# OSPLC2_2_CPU1.net
KiCad netlist of a schematic drawn in Altium Designer
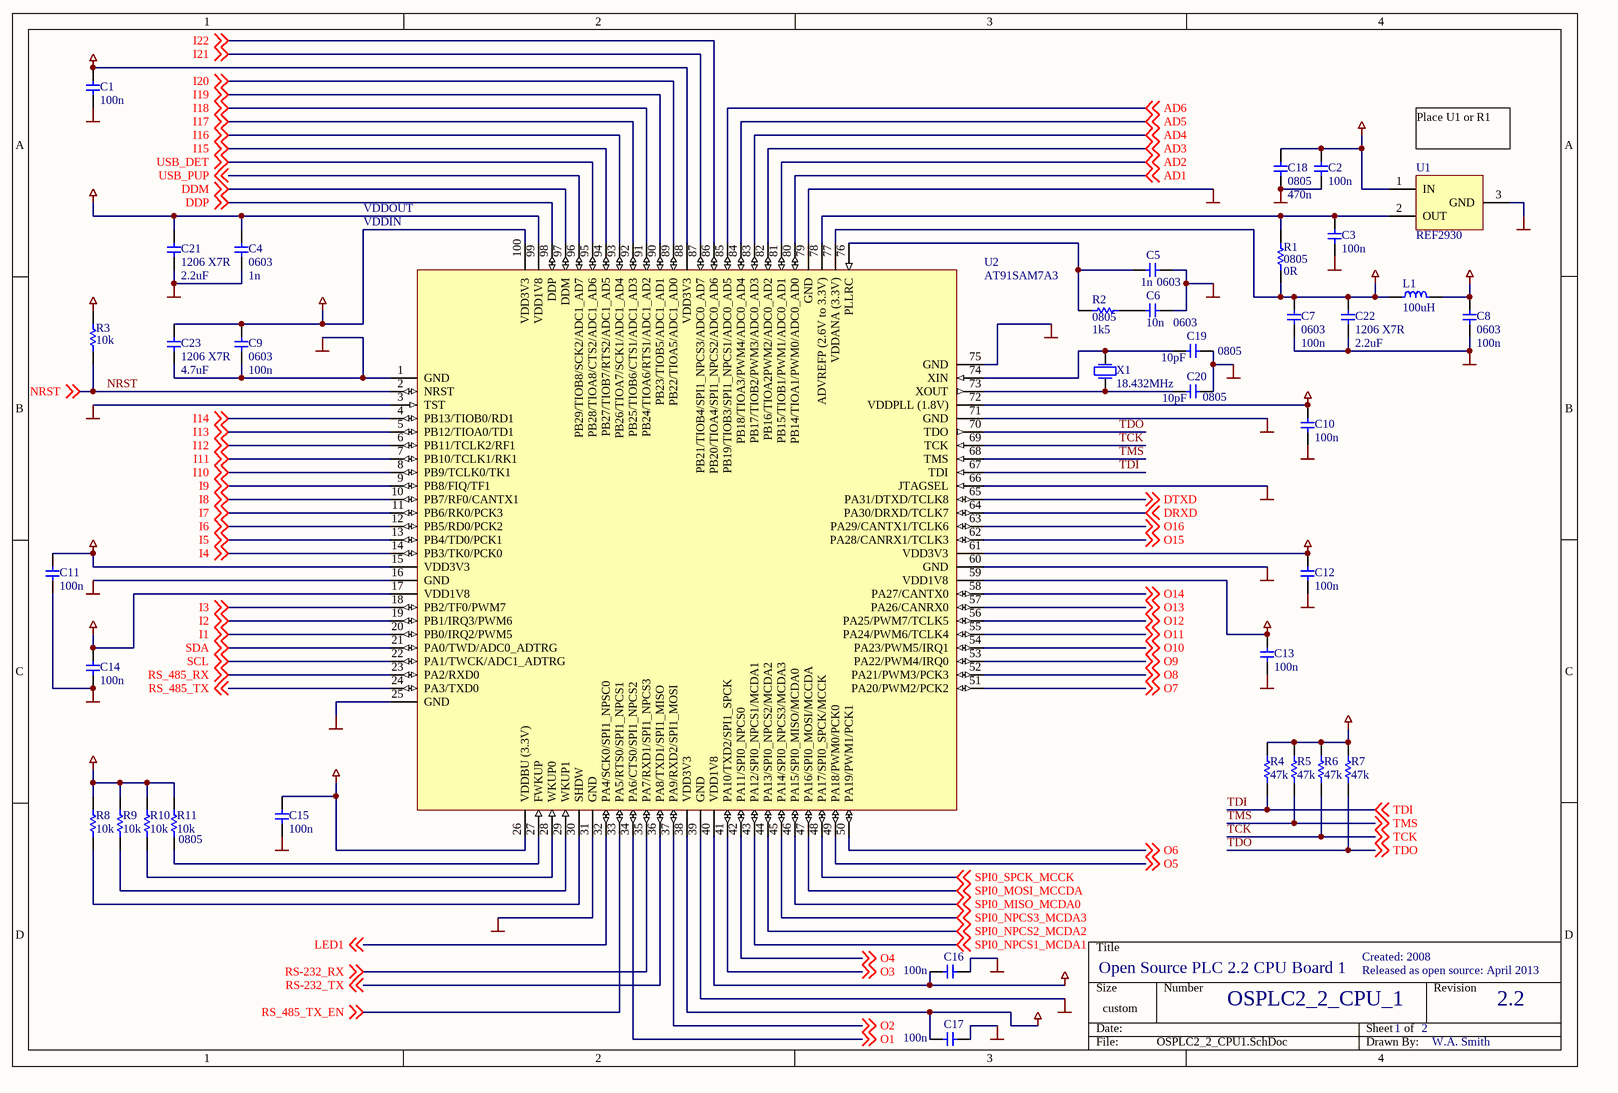
[diagram p0: OSPLC2_2_CPU1.SchDoc]

(export (version "E")
  (design (tool "Eeschema 10.0.6"))
  (components
    (comp (ref "C1")
      (value "0603")
      (footprint "0603")
      (description "0603 footprint non-polorised capacitor")
      (fields (field (name "ALTIUM_VALUE") "100n"))
      (libsource (lib "Integrated Comp_lib") (part "CAP_0603"))
    )
    (comp (ref "C2")
      (value "0603")
      (footprint "0603")
      (description "0603 footprint non-polorised capacitor")
      (fields (field (name "ALTIUM_VALUE") "100n"))
      (libsource (lib "Integrated Comp_lib") (part "CAP_0603"))
    )
    (comp (ref "C3")
      (value "0603")
      (footprint "0603")
      (description "0603 footprint non-polorised capacitor")
      (fields (field (name "ALTIUM_VALUE") "100n"))
      (libsource (lib "Integrated Comp_lib") (part "CAP_0603"))
    )
    (comp (ref "C4")
      (value "0603")
      (footprint "0603")
      (description "0603 footprint non-polorised capacitor")
      (fields (field (name "ALTIUM_VALUE") "1n"))
      (libsource (lib "Integrated Comp_lib") (part "CAP_0603"))
    )
    (comp (ref "C5")
      (value "0603")
      (footprint "0603")
      (description "0603 footprint non-polorised capacitor")
      (fields (field (name "ALTIUM_VALUE") "1n"))
      (libsource (lib "Integrated Comp_lib") (part "CAP_0603"))
    )
    (comp (ref "C6")
      (value "0603")
      (footprint "0603")
      (description "0603 footprint non-polorised capacitor")
      (fields (field (name "ALTIUM_VALUE") "10n"))
      (libsource (lib "Integrated Comp_lib") (part "CAP_0603"))
    )
    (comp (ref "C7")
      (value "0603")
      (footprint "0603")
      (description "0603 footprint non-polorised capacitor")
      (fields (field (name "ALTIUM_VALUE") "100n"))
      (libsource (lib "Integrated Comp_lib") (part "CAP_0603"))
    )
    (comp (ref "C8")
      (value "0603")
      (footprint "0603")
      (description "0603 footprint non-polorised capacitor")
      (fields (field (name "ALTIUM_VALUE") "100n"))
      (libsource (lib "Integrated Comp_lib") (part "CAP_0603"))
    )
    (comp (ref "C9")
      (value "0603")
      (footprint "0603")
      (description "0603 footprint non-polorised capacitor")
      (fields (field (name "ALTIUM_VALUE") "100n"))
      (libsource (lib "Integrated Comp_lib") (part "CAP_0603"))
    )
    (comp (ref "C10")
      (value "0603")
      (footprint "0603")
      (description "0603 footprint non-polorised capacitor")
      (fields (field (name "ALTIUM_VALUE") "100n"))
      (libsource (lib "Integrated Comp_lib") (part "CAP_0603"))
    )
    (comp (ref "C11")
      (value "0603")
      (footprint "0603")
      (description "0603 footprint non-polorised capacitor")
      (fields (field (name "ALTIUM_VALUE") "100n"))
      (libsource (lib "Integrated Comp_lib") (part "CAP_0603"))
    )
    (comp (ref "C12")
      (value "0603")
      (footprint "0603")
      (description "0603 footprint non-polorised capacitor")
      (fields (field (name "ALTIUM_VALUE") "100n"))
      (libsource (lib "Integrated Comp_lib") (part "CAP_0603"))
    )
    (comp (ref "C13")
      (value "0603")
      (footprint "0603")
      (description "0603 footprint non-polorised capacitor")
      (fields (field (name "ALTIUM_VALUE") "100n"))
      (libsource (lib "Integrated Comp_lib") (part "CAP_0603"))
    )
    (comp (ref "C14")
      (value "0603")
      (footprint "0603")
      (description "0603 footprint non-polorised capacitor")
      (fields (field (name "ALTIUM_VALUE") "100n"))
      (libsource (lib "Integrated Comp_lib") (part "CAP_0603"))
    )
    (comp (ref "C15")
      (value "0603")
      (footprint "0603")
      (description "0603 footprint non-polorised capacitor")
      (fields (field (name "ALTIUM_VALUE") "100n"))
      (libsource (lib "Integrated Comp_lib") (part "CAP_0603"))
    )
    (comp (ref "C16")
      (value "0603")
      (footprint "0603")
      (description "0603 footprint non-polorised capacitor")
      (fields (field (name "ALTIUM_VALUE") "100n"))
      (libsource (lib "Integrated Comp_lib") (part "CAP_0603"))
    )
    (comp (ref "C17")
      (value "0603")
      (footprint "0603")
      (description "0603 footprint non-polorised capacitor")
      (fields (field (name "ALTIUM_VALUE") "100n"))
      (libsource (lib "Integrated Comp_lib") (part "CAP_0603"))
    )
    (comp (ref "C18")
      (value "0805")
      (footprint "0805")
      (description "0805 footprint non-polarised capacitor")
      (fields (field (name "ALTIUM_VALUE") "470n"))
      (libsource (lib "Integrated Comp_lib") (part "CAP_0805"))
    )
    (comp (ref "C19")
      (value "0805")
      (footprint "0805")
      (description "0805 footprint non-polarised capacitor")
      (fields (field (name "ALTIUM_VALUE") "10pF"))
      (libsource (lib "Integrated Comp_lib") (part "CAP_0805"))
    )
    (comp (ref "C20")
      (value "0805")
      (footprint "0805")
      (description "0805 footprint non-polarised capacitor")
      (fields (field (name "ALTIUM_VALUE") "10pF"))
      (libsource (lib "Integrated Comp_lib") (part "CAP_0805"))
    )
    (comp (ref "C21")
      (value "1206 X7R")
      (footprint "1206")
      (description "1206 footprint non-polorised capacitor")
      (fields (field (name "ALTIUM_VALUE") "2.2uF"))
      (libsource (lib "Integrated Comp_lib") (part "CAP_1206"))
    )
    (comp (ref "C22")
      (value "1206 X7R")
      (footprint "1206")
      (description "1206 footprint non-polorised capacitor")
      (fields (field (name "ALTIUM_VALUE") "2.2uF"))
      (libsource (lib "Integrated Comp_lib") (part "CAP_1206"))
    )
    (comp (ref "C23")
      (value "1206 X7R")
      (footprint "1206")
      (description "1206 footprint non-polorised capacitor")
      (fields (field (name "ALTIUM_VALUE") "4.7uF"))
      (libsource (lib "Integrated Comp_lib") (part "CAP_1206"))
    )
    (comp (ref "L1")
      (value "100uH")
      (footprint "1206")
      (description "muRata Chip Coil")
      (fields (field (name "PART NO.") "LQH31MN101J03"))
      (libsource (lib "Integrated Comp_lib") (part "INDUCTOR_1206"))
    )
    (comp (ref "R1")
      (value "0805")
      (footprint "0805")
      (description "0805 footprint resistor")
      (fields (field (name "ALTIUM_VALUE") "0R"))
      (libsource (lib "Integrated Comp_lib") (part "RES_0805"))
    )
    (comp (ref "R2")
      (value "0805")
      (footprint "0805")
      (description "0805 footprint resistor")
      (fields (field (name "ALTIUM_VALUE") "1k5"))
      (libsource (lib "Integrated Comp_lib") (part "RES_0805"))
    )
    (comp (ref "R3")
      (value "0805")
      (footprint "0805")
      (description "0805 footprint resistor")
      (fields (field (name "ALTIUM_VALUE") "10k"))
      (libsource (lib "Integrated Comp_lib") (part "RES_0805"))
    )
    (comp (ref "R4")
      (value "0805")
      (footprint "0805")
      (description "0805 footprint resistor")
      (fields (field (name "ALTIUM_VALUE") "47k"))
      (libsource (lib "Integrated Comp_lib") (part "RES_0805"))
    )
    (comp (ref "R5")
      (value "0805")
      (footprint "0805")
      (description "0805 footprint resistor")
      (fields (field (name "ALTIUM_VALUE") "47k"))
      (libsource (lib "Integrated Comp_lib") (part "RES_0805"))
    )
    (comp (ref "R6")
      (value "0805")
      (footprint "0805")
      (description "0805 footprint resistor")
      (fields (field (name "ALTIUM_VALUE") "47k"))
      (libsource (lib "Integrated Comp_lib") (part "RES_0805"))
    )
    (comp (ref "R7")
      (value "0805")
      (footprint "0805")
      (description "0805 footprint resistor")
      (fields (field (name "ALTIUM_VALUE") "47k"))
      (libsource (lib "Integrated Comp_lib") (part "RES_0805"))
    )
    (comp (ref "R8")
      (value "0805")
      (footprint "0805")
      (description "0805 footprint resistor")
      (fields (field (name "ALTIUM_VALUE") "10k"))
      (libsource (lib "Integrated Comp_lib") (part "RES_0805"))
    )
    (comp (ref "R9")
      (value "0805")
      (footprint "0805")
      (description "0805 footprint resistor")
      (fields (field (name "ALTIUM_VALUE") "10k"))
      (libsource (lib "Integrated Comp_lib") (part "RES_0805"))
    )
    (comp (ref "R10")
      (value "0805")
      (footprint "0805")
      (description "0805 footprint resistor")
      (fields (field (name "ALTIUM_VALUE") "10k"))
      (libsource (lib "Integrated Comp_lib") (part "RES_0805"))
    )
    (comp (ref "R11")
      (value "0805")
      (footprint "0805")
      (description "0805 footprint resistor")
      (fields (field (name "ALTIUM_VALUE") "10k"))
      (libsource (lib "Integrated Comp_lib") (part "RES_0805"))
    )
    (comp (ref "U1")
      (value "REF2930")
      (footprint "SOT23-3")
      (description "3V LDO Voltage Reference")
      (libsource (lib "ARM_projects") (part "REF2930"))
    )
    (comp (ref "U2")
      (value "AT91SAM7A3")
      (footprint "F-QFP14x14-G100/X.3N")
      (description "Atmel AT91 ARM Microcontroller with CAN ports")
      (libsource (lib "ARM_projects") (part "AT91SAM7A3"))
    )
    (comp (ref "X1")
      (value "18.432MHz")
      (footprint "CRYSTAL_SMT")
      (description "SMT crystal")
      (libsource (lib "ARM_projects") (part "CRYSTAL_SMT"))
    )
  )
  (nets
    (net (code "1") (name "AD1") (class "Default")
      (node (ref "U2") (pin "80") (pinfunction "PB14/TIOA1/PWM0/ADC0_AD0_80") (pintype "bidirectional"))
    )
    (net (code "2") (name "AD2") (class "Default")
      (node (ref "U2") (pin "81") (pinfunction "PB15/TIOB1/PWM1/ADC0_AD1_81") (pintype "bidirectional"))
    )
    (net (code "3") (name "AD3") (class "Default")
      (node (ref "U2") (pin "82") (pinfunction "PB16/TIOA2PWM2/ADC0_AD2_82") (pintype "bidirectional"))
    )
    (net (code "4") (name "AD4") (class "Default")
      (node (ref "U2") (pin "83") (pinfunction "PB17/TIOB2/PWM3/ADC0_AD3_83") (pintype "bidirectional"))
    )
    (net (code "5") (name "AD5") (class "Default")
      (node (ref "U2") (pin "84") (pinfunction "PB18/TIOA3/PWM4/ADC0_AD4_84") (pintype "bidirectional"))
    )
    (net (code "6") (name "AD6") (class "Default")
      (node (ref "U2") (pin "85") (pinfunction "PB19/TIOB3/SPI1_NPCS1/ADC0_AD5_85") (pintype "bidirectional"))
    )
    (net (code "7") (name "ADC3v3") (class "Default")
      (node (ref "C18") (pin "2") (pinfunction "2_2") (pintype "passive"))
      (node (ref "C2") (pin "2") (pinfunction "2_2") (pintype "passive"))
      (node (ref "C22") (pin "2") (pinfunction "2_2") (pintype "passive"))
      (node (ref "C7") (pin "2") (pinfunction "2_2") (pintype "passive"))
      (node (ref "L1") (pin "1") (pinfunction "1_1") (pintype "passive"))
      (node (ref "R1") (pin "1") (pinfunction "1_1") (pintype "passive"))
      (node (ref "U1") (pin "1") (pinfunction "IN_1") (pintype "power_in"))
      (node (ref "U2") (pin "77") (pinfunction "VDDANA_(3.3V)_77") (pintype "power_in"))
    )
    (net (code "8") (name "DDM") (class "Default")
      (node (ref "U2") (pin "97") (pinfunction "DDM_97") (pintype "bidirectional"))
    )
    (net (code "9") (name "DDP") (class "Default")
      (node (ref "U2") (pin "98") (pinfunction "DDP_98") (pintype "bidirectional"))
    )
    (net (code "10") (name "DRXD") (class "Default")
      (node (ref "U2") (pin "64") (pinfunction "PA30/DRXD/TCLK7_64") (pintype "bidirectional"))
    )
    (net (code "11") (name "DTXD") (class "Default")
      (node (ref "U2") (pin "65") (pinfunction "PA31/DTXD/TCLK8_65") (pintype "bidirectional"))
    )
    (net (code "12") (name "GND") (class "Default")
      (node (ref "C1") (pin "1") (pinfunction "1_1") (pintype "passive"))
      (node (ref "C10") (pin "1") (pinfunction "1_1") (pintype "passive"))
      (node (ref "C11") (pin "1") (pinfunction "1_1") (pintype "passive"))
      (node (ref "C12") (pin "1") (pinfunction "1_1") (pintype "passive"))
      (node (ref "C13") (pin "1") (pinfunction "1_1") (pintype "passive"))
      (node (ref "C14") (pin "1") (pinfunction "1_1") (pintype "passive"))
      (node (ref "C15") (pin "1") (pinfunction "1_1") (pintype "passive"))
      (node (ref "C16") (pin "1") (pinfunction "1_1") (pintype "passive"))
      (node (ref "C17") (pin "1") (pinfunction "1_1") (pintype "passive"))
      (node (ref "C18") (pin "1") (pinfunction "1_1") (pintype "passive"))
      (node (ref "C19") (pin "2") (pinfunction "2_2") (pintype "passive"))
      (node (ref "C2") (pin "1") (pinfunction "1_1") (pintype "passive"))
      (node (ref "C20") (pin "2") (pinfunction "2_2") (pintype "passive"))
      (node (ref "C21") (pin "1") (pinfunction "1_1") (pintype "passive"))
      (node (ref "C22") (pin "1") (pinfunction "1_1") (pintype "passive"))
      (node (ref "C23") (pin "1") (pinfunction "1_1") (pintype "passive"))
      (node (ref "C3") (pin "1") (pinfunction "1_1") (pintype "passive"))
      (node (ref "C4") (pin "1") (pinfunction "1_1") (pintype "passive"))
      (node (ref "C5") (pin "2") (pinfunction "2_2") (pintype "passive"))
      (node (ref "C6") (pin "2") (pinfunction "2_2") (pintype "passive"))
      (node (ref "C7") (pin "1") (pinfunction "1_1") (pintype "passive"))
      (node (ref "C8") (pin "1") (pinfunction "1_1") (pintype "passive"))
      (node (ref "C9") (pin "1") (pinfunction "1_1") (pintype "passive"))
      (node (ref "U1") (pin "3") (pinfunction "GND_3") (pintype "power_in"))
      (node (ref "U2") (pin "1") (pinfunction "GND_1") (pintype "power_in"))
      (node (ref "U2") (pin "16") (pinfunction "GND_16") (pintype "power_in"))
      (node (ref "U2") (pin "25") (pinfunction "GND_25") (pintype "power_in"))
      (node (ref "U2") (pin "3") (pinfunction "TST_3") (pintype "input"))
      (node (ref "U2") (pin "31") (pinfunction "GND_31") (pintype "power_in"))
      (node (ref "U2") (pin "39") (pinfunction "GND_39") (pintype "power_in"))
      (node (ref "U2") (pin "60") (pinfunction "GND_60") (pintype "power_in"))
      (node (ref "U2") (pin "66") (pinfunction "JTAGSEL_66") (pintype "input"))
      (node (ref "U2") (pin "71") (pinfunction "GND_71") (pintype "power_in"))
      (node (ref "U2") (pin "75") (pinfunction "GND_75") (pintype "power_in"))
      (node (ref "U2") (pin "79") (pinfunction "GND_79") (pintype "power_in"))
    )
    (net (code "13") (name "I1") (class "Default")
      (node (ref "U2") (pin "20") (pinfunction "PB0/IRQ2/PWM5_20") (pintype "bidirectional"))
    )
    (net (code "14") (name "I2") (class "Default")
      (node (ref "U2") (pin "19") (pinfunction "PB1/IRQ3/PWM6_19") (pintype "bidirectional"))
    )
    (net (code "15") (name "I3") (class "Default")
      (node (ref "U2") (pin "18") (pinfunction "PB2/TF0/PWM7_18") (pintype "bidirectional"))
    )
    (net (code "16") (name "I4") (class "Default")
      (node (ref "U2") (pin "14") (pinfunction "PB3/TK0/PCK0_14") (pintype "bidirectional"))
    )
    (net (code "17") (name "I5") (class "Default")
      (node (ref "U2") (pin "13") (pinfunction "PB4/TD0/PCK1_13") (pintype "bidirectional"))
    )
    (net (code "18") (name "I6") (class "Default")
      (node (ref "U2") (pin "12") (pinfunction "PB5/RD0/PCK2_12") (pintype "bidirectional"))
    )
    (net (code "19") (name "I7") (class "Default")
      (node (ref "U2") (pin "11") (pinfunction "PB6/RK0/PCK3_11") (pintype "bidirectional"))
    )
    (net (code "20") (name "I8") (class "Default")
      (node (ref "U2") (pin "10") (pinfunction "PB7/RF0/CANTX1_10") (pintype "bidirectional"))
    )
    (net (code "21") (name "I9") (class "Default")
      (node (ref "U2") (pin "9") (pinfunction "PB8/FIQ/TF1_9") (pintype "bidirectional"))
    )
    (net (code "22") (name "I10") (class "Default")
      (node (ref "U2") (pin "8") (pinfunction "PB9/TCLK0/TK1_8") (pintype "bidirectional"))
    )
    (net (code "23") (name "I11") (class "Default")
      (node (ref "U2") (pin "7") (pinfunction "PB10/TCLK1/RK1_7") (pintype "bidirectional"))
    )
    (net (code "24") (name "I12") (class "Default")
      (node (ref "U2") (pin "6") (pinfunction "PB11/TCLK2/RF1_6") (pintype "bidirectional"))
    )
    (net (code "25") (name "I13") (class "Default")
      (node (ref "U2") (pin "5") (pinfunction "PB12/TIOA0/TD1_5") (pintype "bidirectional"))
    )
    (net (code "26") (name "I14") (class "Default")
      (node (ref "U2") (pin "4") (pinfunction "PB13/TIOB0/RD1_4") (pintype "bidirectional"))
    )
    (net (code "27") (name "I15") (class "Default")
      (node (ref "U2") (pin "94") (pinfunction "PB27/TIOB7/RTS2/ADC1_AD5_94") (pintype "bidirectional"))
    )
    (net (code "28") (name "I16") (class "Default")
      (node (ref "U2") (pin "93") (pinfunction "PB26/TIOA7/SCK1/ADC1_AD4_93") (pintype "bidirectional"))
    )
    (net (code "29") (name "I17") (class "Default")
      (node (ref "U2") (pin "92") (pinfunction "PB25/TIOB6/CTS1/ADC1_AD3_92") (pintype "bidirectional"))
    )
    (net (code "30") (name "I18") (class "Default")
      (node (ref "U2") (pin "91") (pinfunction "PB24/TIOA6/RTS1/ADC1_AD2_91") (pintype "bidirectional"))
    )
    (net (code "31") (name "I19") (class "Default")
      (node (ref "U2") (pin "90") (pinfunction "PB23/TIOB5/ADC1_AD1_90") (pintype "bidirectional"))
    )
    (net (code "32") (name "I20") (class "Default")
      (node (ref "U2") (pin "89") (pinfunction "PB22/TIOA5/ADC1_AD0_89") (pintype "bidirectional"))
    )
    (net (code "33") (name "I21") (class "Default")
      (node (ref "U2") (pin "87") (pinfunction "PB21/TIOB4/SPI1_NPCS3/ADC0_AD7_87") (pintype "bidirectional"))
    )
    (net (code "34") (name "I22") (class "Default")
      (node (ref "U2") (pin "86") (pinfunction "PB20/TIOA4/SPI1_NPCS2/ADC0_AD6_86") (pintype "bidirectional"))
    )
    (net (code "35") (name "LED1") (class "Default")
      (node (ref "U2") (pin "32") (pinfunction "PA4/SCK0/SPI1_NPSC0_32") (pintype "bidirectional"))
    )
    (net (code "36") (name "NRST") (class "Default")
      (node (ref "R3") (pin "1") (pinfunction "1_1") (pintype "passive"))
      (node (ref "U2") (pin "2") (pinfunction "NRST_2") (pintype "bidirectional"))
    )
    (net (code "37") (name "Net-(C6-Pad1)") (class "Default")
      (node (ref "C6") (pin "1") (pinfunction "1_1") (pintype "passive"))
      (node (ref "R2") (pin "2") (pinfunction "2_2") (pintype "passive"))
    )
    (net (code "38") (name "Net-(U1-OUT)") (class "Default")
      (node (ref "C3") (pin "2") (pinfunction "2_2") (pintype "passive"))
      (node (ref "R1") (pin "2") (pinfunction "2_2") (pintype "passive"))
      (node (ref "U1") (pin "2") (pinfunction "OUT_2") (pintype "power_in"))
      (node (ref "U2") (pin "78") (pinfunction "ADVREFP_(2.6V_to_3.3V)_78") (pintype "power_in"))
    )
    (net (code "39") (name "Net-(U2-FWKUP)") (class "Default")
      (node (ref "R11") (pin "1") (pinfunction "1_1") (pintype "passive"))
      (node (ref "U2") (pin "27") (pinfunction "FWKUP_27") (pintype "input"))
    )
    (net (code "40") (name "Net-(U2-PLLRC)") (class "Default")
      (node (ref "C5") (pin "1") (pinfunction "1_1") (pintype "passive"))
      (node (ref "R2") (pin "1") (pinfunction "1_1") (pintype "passive"))
      (node (ref "U2") (pin "76") (pinfunction "PLLRC_76") (pintype "input"))
    )
    (net (code "41") (name "Net-(U2-SHDW)") (class "Default")
      (node (ref "R8") (pin "1") (pinfunction "1_1") (pintype "passive"))
      (node (ref "U2") (pin "30") (pinfunction "SHDW_30") (pintype "open_collector"))
    )
    (net (code "42") (name "Net-(U2-WKUP0)") (class "Default")
      (node (ref "R10") (pin "1") (pinfunction "1_1") (pintype "passive"))
      (node (ref "U2") (pin "28") (pinfunction "WKUP0_28") (pintype "input"))
    )
    (net (code "43") (name "Net-(U2-WKUP1)") (class "Default")
      (node (ref "R9") (pin "1") (pinfunction "1_1") (pintype "passive"))
      (node (ref "U2") (pin "29") (pinfunction "WKUP1_29") (pintype "input"))
    )
    (net (code "44") (name "Net-(U2-XIN)") (class "Default")
      (node (ref "C19") (pin "1") (pinfunction "1_1") (pintype "passive"))
      (node (ref "U2") (pin "74") (pinfunction "XIN_74") (pintype "input"))
      (node (ref "X1") (pin "1") (pinfunction "X_1") (pintype "passive"))
    )
    (net (code "45") (name "Net-(U2-XOUT)") (class "Default")
      (node (ref "C20") (pin "1") (pinfunction "1_1") (pintype "passive"))
      (node (ref "U2") (pin "73") (pinfunction "XOUT_73") (pintype "output"))
      (node (ref "X1") (pin "2") (pinfunction "X_2") (pintype "passive"))
    )
    (net (code "46") (name "O1") (class "Default")
      (node (ref "U2") (pin "34") (pinfunction "PA6/CTS0/SPI1_NPCS2_34") (pintype "bidirectional"))
    )
    (net (code "47") (name "O2") (class "Default")
      (node (ref "U2") (pin "37") (pinfunction "PA9/RXD2/SPI1_MOSI_37") (pintype "bidirectional"))
    )
    (net (code "48") (name "O3") (class "Default")
      (node (ref "U2") (pin "41") (pinfunction "PA10/TXD2/SPI1_SPCK_41") (pintype "bidirectional"))
    )
    (net (code "49") (name "O4") (class "Default")
      (node (ref "U2") (pin "42") (pinfunction "PA11/SPI0_NPCS0_42") (pintype "bidirectional"))
    )
    (net (code "50") (name "O5") (class "Default")
      (node (ref "U2") (pin "49") (pinfunction "PA18/PWM0/PCK0_49") (pintype "bidirectional"))
    )
    (net (code "51") (name "O6") (class "Default")
      (node (ref "U2") (pin "50") (pinfunction "PA19/PWM1/PCK1_50") (pintype "bidirectional"))
    )
    (net (code "52") (name "O7") (class "Default")
      (node (ref "U2") (pin "51") (pinfunction "PA20/PWM2/PCK2_51") (pintype "bidirectional"))
    )
    (net (code "53") (name "O8") (class "Default")
      (node (ref "U2") (pin "52") (pinfunction "PA21/PWM3/PCK3_52") (pintype "bidirectional"))
    )
    (net (code "54") (name "O9") (class "Default")
      (node (ref "U2") (pin "53") (pinfunction "PA22/PWM4/IRQ0_53") (pintype "bidirectional"))
    )
    (net (code "55") (name "O10") (class "Default")
      (node (ref "U2") (pin "54") (pinfunction "PA23/PWM5/IRQ1_54") (pintype "bidirectional"))
    )
    (net (code "56") (name "O11") (class "Default")
      (node (ref "U2") (pin "55") (pinfunction "PA24/PWM6/TCLK4_55") (pintype "bidirectional"))
    )
    (net (code "57") (name "O12") (class "Default")
      (node (ref "U2") (pin "56") (pinfunction "PA25/PWM7/TCLK5_56") (pintype "bidirectional"))
    )
    (net (code "58") (name "O13") (class "Default")
      (node (ref "U2") (pin "57") (pinfunction "PA26/CANRX0_57") (pintype "bidirectional"))
    )
    (net (code "59") (name "O14") (class "Default")
      (node (ref "U2") (pin "58") (pinfunction "PA27/CANTX0_58") (pintype "bidirectional"))
    )
    (net (code "60") (name "O15") (class "Default")
      (node (ref "U2") (pin "62") (pinfunction "PA28/CANRX1/TCLK3_62") (pintype "bidirectional"))
    )
    (net (code "61") (name "O16") (class "Default")
      (node (ref "U2") (pin "63") (pinfunction "PA29/CANTX1/TCLK6_63") (pintype "bidirectional"))
    )
    (net (code "62") (name "RS-232_RX") (class "Default")
      (node (ref "U2") (pin "35") (pinfunction "PA7/RXD1/SPI1_NPCS3_35") (pintype "bidirectional"))
    )
    (net (code "63") (name "RS-232_TX") (class "Default")
      (node (ref "U2") (pin "36") (pinfunction "PA8/TXD1/SPI1_MISO_36") (pintype "bidirectional"))
    )
    (net (code "64") (name "RS_485_RX") (class "Default")
      (node (ref "U2") (pin "23") (pinfunction "PA2/RXD0_23") (pintype "bidirectional"))
    )
    (net (code "65") (name "RS_485_TX") (class "Default")
      (node (ref "U2") (pin "24") (pinfunction "PA3/TXD0_24") (pintype "bidirectional"))
    )
    (net (code "66") (name "RS_485_TX_EN") (class "Default")
      (node (ref "U2") (pin "33") (pinfunction "PA5/RTS0/SPI1_NPCS1_33") (pintype "bidirectional"))
    )
    (net (code "67") (name "SCL") (class "Default")
      (node (ref "U2") (pin "22") (pinfunction "PA1/TWCK/ADC1_ADTRG_22") (pintype "bidirectional"))
    )
    (net (code "68") (name "SDA") (class "Default")
      (node (ref "U2") (pin "21") (pinfunction "PA0/TWD/ADC0_ADTRG_21") (pintype "bidirectional"))
    )
    (net (code "69") (name "SPI0_MISO_MCDA0") (class "Default")
      (node (ref "U2") (pin "46") (pinfunction "PA15/SPI0_MISO/MCDA0_46") (pintype "bidirectional"))
    )
    (net (code "70") (name "SPI0_MOSI_MCCDA") (class "Default")
      (node (ref "U2") (pin "47") (pinfunction "PA16/SPI0_MOSI/MCCDA_47") (pintype "bidirectional"))
    )
    (net (code "71") (name "SPI0_NPCS1_MCDA1") (class "Default")
      (node (ref "U2") (pin "43") (pinfunction "PA12/SPI0_NPCS1/MCDA1_43") (pintype "bidirectional"))
    )
    (net (code "72") (name "SPI0_NPCS2_MCDA2") (class "Default")
      (node (ref "U2") (pin "44") (pinfunction "PA13/SPI0_NPCS2/MCDA2_44") (pintype "bidirectional"))
    )
    (net (code "73") (name "SPI0_NPCS3_MCDA3") (class "Default")
      (node (ref "U2") (pin "45") (pinfunction "PA14/SPI0_NPCS3/MCDA3_45") (pintype "bidirectional"))
    )
    (net (code "74") (name "SPI0_SPCK_MCCK") (class "Default")
      (node (ref "U2") (pin "48") (pinfunction "PA17/SPI0_SPCK/MCCK_48") (pintype "bidirectional"))
    )
    (net (code "75") (name "TCK") (class "Default")
      (node (ref "R6") (pin "1") (pinfunction "1_1") (pintype "passive"))
      (node (ref "U2") (pin "69") (pinfunction "TCK_69") (pintype "input"))
    )
    (net (code "76") (name "TDI") (class "Default")
      (node (ref "R4") (pin "1") (pinfunction "1_1") (pintype "passive"))
      (node (ref "U2") (pin "67") (pinfunction "TDI_67") (pintype "input"))
    )
    (net (code "77") (name "TDO") (class "Default")
      (node (ref "R7") (pin "1") (pinfunction "1_1") (pintype "passive"))
      (node (ref "U2") (pin "70") (pinfunction "TDO_70") (pintype "output"))
    )
    (net (code "78") (name "TMS") (class "Default")
      (node (ref "R5") (pin "1") (pinfunction "1_1") (pintype "passive"))
      (node (ref "U2") (pin "68") (pinfunction "TMS_68") (pintype "input"))
    )
    (net (code "79") (name "USB_DET") (class "Default")
      (node (ref "U2") (pin "95") (pinfunction "PB28/TIOA8/CTS2/ADC1_AD6_95") (pintype "bidirectional"))
    )
    (net (code "80") (name "USB_PUP") (class "Default")
      (node (ref "U2") (pin "96") (pinfunction "PB29/TIOB8/SCK2/ADC1_AD7_96") (pintype "bidirectional"))
    )
    (net (code "81") (name "VCC1v8") (class "Default")
      (node (ref "C10") (pin "2") (pinfunction "2_2") (pintype "passive"))
      (node (ref "C13") (pin "2") (pinfunction "2_2") (pintype "passive"))
      (node (ref "C14") (pin "2") (pinfunction "2_2") (pintype "passive"))
      (node (ref "C16") (pin "2") (pinfunction "2_2") (pintype "passive"))
      (node (ref "C21") (pin "2") (pinfunction "2_2") (pintype "passive"))
      (node (ref "C4") (pin "2") (pinfunction "2_2") (pintype "passive"))
      (node (ref "U2") (pin "17") (pinfunction "VDD1V8_17") (pintype "power_in"))
      (node (ref "U2") (pin "40") (pinfunction "VDD1V8_40") (pintype "power_in"))
      (node (ref "U2") (pin "59") (pinfunction "VDD1V8_59") (pintype "power_in"))
      (node (ref "U2") (pin "72") (pinfunction "VDDPLL_(1.8V)_72") (pintype "power_in"))
      (node (ref "U2") (pin "99") (pinfunction "VDD1V8_99") (pintype "power_in"))
    )
    (net (code "82") (name "VCC3v3") (class "Default")
      (node (ref "C1") (pin "2") (pinfunction "2_2") (pintype "passive"))
      (node (ref "C11") (pin "2") (pinfunction "2_2") (pintype "passive"))
      (node (ref "C12") (pin "2") (pinfunction "2_2") (pintype "passive"))
      (node (ref "C15") (pin "2") (pinfunction "2_2") (pintype "passive"))
      (node (ref "C17") (pin "2") (pinfunction "2_2") (pintype "passive"))
      (node (ref "C23") (pin "2") (pinfunction "2_2") (pintype "passive"))
      (node (ref "C8") (pin "2") (pinfunction "2_2") (pintype "passive"))
      (node (ref "C9") (pin "2") (pinfunction "2_2") (pintype "passive"))
      (node (ref "L1") (pin "2") (pinfunction "2_2") (pintype "passive"))
      (node (ref "R10") (pin "2") (pinfunction "2_2") (pintype "passive"))
      (node (ref "R11") (pin "2") (pinfunction "2_2") (pintype "passive"))
      (node (ref "R3") (pin "2") (pinfunction "2_2") (pintype "passive"))
      (node (ref "R4") (pin "2") (pinfunction "2_2") (pintype "passive"))
      (node (ref "R5") (pin "2") (pinfunction "2_2") (pintype "passive"))
      (node (ref "R6") (pin "2") (pinfunction "2_2") (pintype "passive"))
      (node (ref "R7") (pin "2") (pinfunction "2_2") (pintype "passive"))
      (node (ref "R8") (pin "2") (pinfunction "2_2") (pintype "passive"))
      (node (ref "R9") (pin "2") (pinfunction "2_2") (pintype "passive"))
      (node (ref "U2") (pin "100") (pinfunction "VDD3V3_100") (pintype "power_in"))
      (node (ref "U2") (pin "15") (pinfunction "VDD3V3_15") (pintype "power_in"))
      (node (ref "U2") (pin "26") (pinfunction "VDDBU_(3.3V)_26") (pintype "power_in"))
      (node (ref "U2") (pin "38") (pinfunction "VDD3V3_38") (pintype "power_in"))
      (node (ref "U2") (pin "61") (pinfunction "VDD3V3_61") (pintype "power_in"))
      (node (ref "U2") (pin "88") (pinfunction "VDD3V3_88") (pintype "power_in"))
    )
  )
)
